# PushButton.net
KiCad netlist of a schematic drawn in Altium Designer
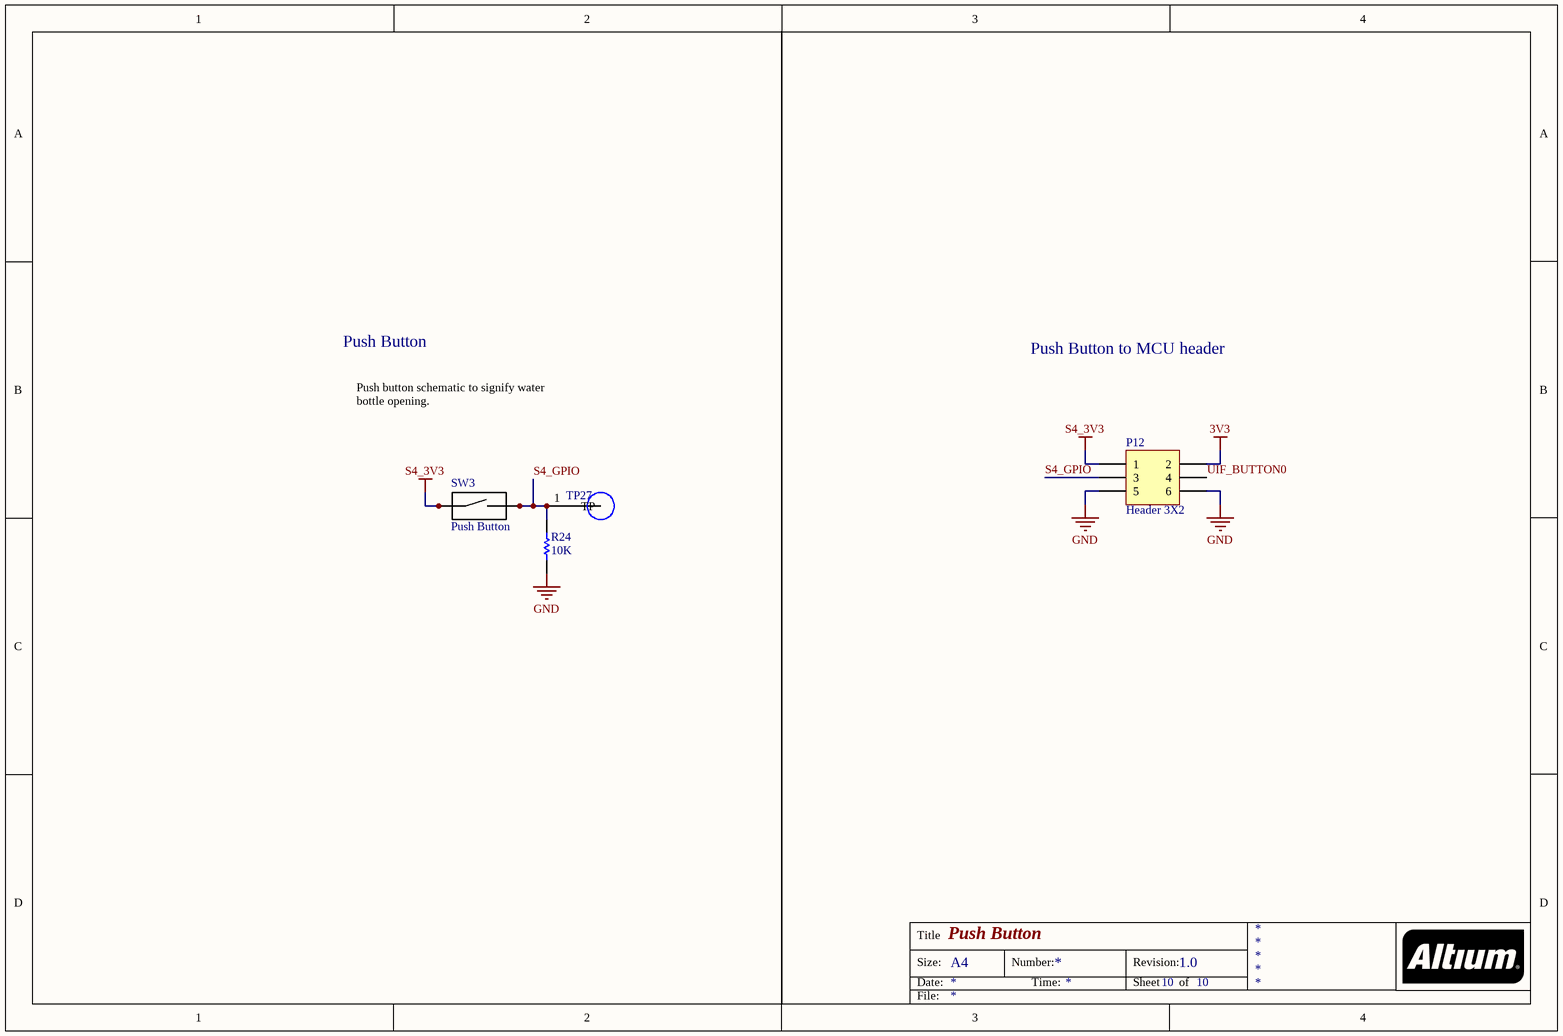
[diagram p0: PushButton.SchDoc]

(export (version "E")
  (design (tool "Eeschema 10.0.6"))
  (components
    (comp (ref "P12")
      (value "Header 3X2")
      (footprint "HDR2X3")
      (description "Header, 3-Pin, Dual row")
      (fields
        (field (name "DIGI-KEY PART NUMBER") "609-3237-ND")
        (field (name "MANUFACTURER") "Amphenol ICC (FCI)")
      )
      (libsource (lib "Miscellaneous Connectors") (part "Header 3X2"))
    )
    (comp (ref "R24")
      (value "10K")
      (footprint "1608[0603]")
      (description "RES 10K OHM 1% 1/8W 0603")
      (fields
        (field (name "DIGI-KEY PART NUMBER") "RNCP0603FTD10K0CT-ND")
        (field (name "MANUFACTURER") "Stackpole Electronics Inc")
      )
      (libsource (lib "Miscellaneous Devices") (part "Res1"))
    )
    (comp (ref "SW3")
      (value "Push Button")
      (footprint "Push Button")
      (description "SWITCH TACTILE SPST-NO 0.05A 24V")
      (fields
        (field (name "DIGI-KEY PART NUMBER") "450-2058-1-ND")
        (field (name "MANUFACTURER") "TE Connectivity ALCOSWITCH Switches")
      )
      (libsource (lib "Hydrated_Buffs") (part "Push Button"))
    )
    (comp (ref "TP27")
      (value "TP")
      (footprint "TP")
      (description "PC TEST POINT MINIATURE")
      (fields
        (field (name "MANUFACTURER") "Keystone Electronics")
        (field (name "DIGI-KEY PART NUMBER") "36-5019CT-ND")
      )
      (libsource (lib "TP") (part "TP"))
    )
  )
  (nets
    (net (code "1") (name "/S4_GPIO") (class "Default")
      (node (ref "P12") (pin "3") (pinfunction "3_3") (pintype "passive"))
      (node (ref "R24") (pin "2") (pinfunction "2_2") (pintype "passive"))
      (node (ref "SW3") (pin "1") (pinfunction "2_1") (pintype "passive"))
      (node (ref "SW3") (pin "2") (pinfunction "2_2") (pintype "passive"))
      (node (ref "TP27") (pin "1") (pinfunction "TP_1") (pintype "passive"))
    )
    (net (code "2") (name "/UIF_BUTTON0") (class "Default")
      (node (ref "P12") (pin "4") (pinfunction "4_4") (pintype "passive"))
    )
    (net (code "3") (name "3V3") (class "Default")
      (node (ref "P12") (pin "2") (pinfunction "2_2") (pintype "passive"))
    )
    (net (code "4") (name "GND") (class "Default")
      (node (ref "P12") (pin "5") (pinfunction "5_5") (pintype "passive"))
      (node (ref "P12") (pin "6") (pinfunction "6_6") (pintype "passive"))
      (node (ref "R24") (pin "1") (pinfunction "1_1") (pintype "passive"))
    )
    (net (code "5") (name "S4_3V3") (class "Default")
      (node (ref "P12") (pin "1") (pinfunction "1_1") (pintype "passive"))
      (node (ref "SW3") (pin "3") (pinfunction "1_3") (pintype "passive"))
      (node (ref "SW3") (pin "4") (pinfunction "1_4") (pintype "passive"))
    )
  )
)
